# 07_-_SD.net
KiCad netlist of a schematic drawn in Altium Designer
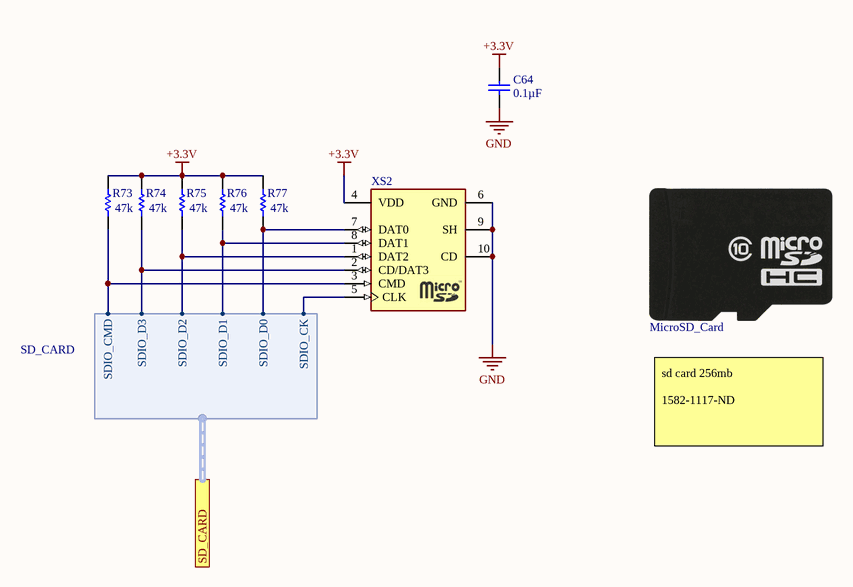
[diagram p0: [07] - SD.SchDoc]

(export (version "E")
  (design (tool "Eeschema 10.0.6"))
  (components
    (comp (ref "*1")
      (value "MicroSD_Card")
      (fields
        (field (name "MANUFACTURER") "Apacer")
        (field (name "MANUFACTURER PART NUMBER") "AP-MSD256ISI-1T")
      )
      (libsource (lib "Light_Control_BM-v.1.0-2018") (part "MicroSD_Card"))
    )
    (comp (ref "C64")
      (value "Capacitor")
      (footprint "Cap 0603")
      (description "Chip Capacitor Nonpolar")
      (fields
        (field (name "MANUFACTURER") "Kemet")
        (field (name "MANUFACTURER PART NUMBER") "C0603C104K5RACTU")
        (field (name "CAPACITANCE") "0.1µF")
      )
      (libsource (lib "Altium_Library") (part "Capacitor"))
    )
    (comp (ref "R73")
      (value "Res1")
      (footprint "Res-0603")
      (description "Chip Resistor")
      (fields
        (field (name "MANUFACTURER") "Panasonic")
        (field (name "MANUFACTURER PART NUMBER") "ERJ-3EKF4702V")
        (field (name "RESISTANCE") "47k")
      )
      (libsource (lib "Altium_Library") (part "Res1"))
    )
    (comp (ref "R74")
      (value "Res1")
      (footprint "Res-0603")
      (description "Chip Resistor")
      (fields
        (field (name "MANUFACTURER") "Panasonic")
        (field (name "MANUFACTURER PART NUMBER") "ERJ-3EKF4702V")
        (field (name "RESISTANCE") "47k")
      )
      (libsource (lib "Altium_Library") (part "Res1"))
    )
    (comp (ref "R75")
      (value "Res1")
      (footprint "Res-0603")
      (description "Chip Resistor")
      (fields
        (field (name "MANUFACTURER") "Panasonic")
        (field (name "MANUFACTURER PART NUMBER") "ERJ-3EKF4702V")
        (field (name "RESISTANCE") "47k")
      )
      (libsource (lib "Altium_Library") (part "Res1"))
    )
    (comp (ref "R76")
      (value "Res1")
      (footprint "Res-0603")
      (description "Chip Resistor")
      (fields
        (field (name "MANUFACTURER") "Panasonic")
        (field (name "MANUFACTURER PART NUMBER") "ERJ-3EKF4702V")
        (field (name "RESISTANCE") "47k")
      )
      (libsource (lib "Altium_Library") (part "Res1"))
    )
    (comp (ref "R77")
      (value "Res1")
      (footprint "Res-0603")
      (description "Chip Resistor")
      (fields
        (field (name "MANUFACTURER") "Panasonic")
        (field (name "MANUFACTURER PART NUMBER") "ERJ-3EKF4702V")
        (field (name "RESISTANCE") "47k")
      )
      (libsource (lib "Altium_Library") (part "Res1"))
    )
    (comp (ref "XS2")
      (value "~")
      (footprint "MICROSD")
      (description "=Description")
      (fields (field (name "MANUFACTURER") "Molex") (field (name "MANUFACTURER PART NUMBER") "105162-0001"))
      (libsource (lib "CVC_Meter") (part "MICROSD"))
    )
  )
  (nets
    (net (code "2") (name "+3.3V") (class "Default")
      (node (ref "C64") (pin "2") (pinfunction "2_2") (pintype "passive"))
      (node (ref "R73") (pin "2") (pinfunction "2_2") (pintype "passive"))
      (node (ref "R74") (pin "2") (pinfunction "2_2") (pintype "passive"))
      (node (ref "R75") (pin "2") (pinfunction "2_2") (pintype "passive"))
      (node (ref "R76") (pin "2") (pinfunction "2_2") (pintype "passive"))
      (node (ref "R77") (pin "2") (pinfunction "2_2") (pintype "passive"))
      (node (ref "XS2") (pin "4") (pinfunction "VDD_4") (pintype "power_in"))
    )
    (net (code "3") (name "/SDIO_CK") (class "Default")
      (node (ref "XS2") (pin "5") (pinfunction "CLK_5") (pintype "input"))
    )
    (net (code "4") (name "/SDIO_CMD") (class "Default")
      (node (ref "R73") (pin "1") (pinfunction "1_1") (pintype "passive"))
      (node (ref "XS2") (pin "3") (pinfunction "CMD_3") (pintype "input"))
    )
    (net (code "5") (name "/SDIO_D0") (class "Default")
      (node (ref "R77") (pin "1") (pinfunction "1_1") (pintype "passive"))
      (node (ref "XS2") (pin "7") (pinfunction "DAT0_7") (pintype "bidirectional"))
    )
    (net (code "6") (name "/SDIO_D1") (class "Default")
      (node (ref "R76") (pin "1") (pinfunction "1_1") (pintype "passive"))
      (node (ref "XS2") (pin "8") (pinfunction "DAT1_8") (pintype "bidirectional"))
    )
    (net (code "7") (name "/SDIO_D2") (class "Default")
      (node (ref "R75") (pin "1") (pinfunction "1_1") (pintype "passive"))
      (node (ref "XS2") (pin "1") (pinfunction "DAT2_1") (pintype "bidirectional"))
    )
    (net (code "8") (name "/SDIO_D3") (class "Default")
      (node (ref "R74") (pin "1") (pinfunction "1_1") (pintype "passive"))
      (node (ref "XS2") (pin "2") (pinfunction "CD/DAT3_2") (pintype "bidirectional"))
    )
    (net (code "10") (name "GND") (class "Default")
      (node (ref "C64") (pin "1") (pinfunction "1_1") (pintype "passive"))
      (node (ref "XS2") (pin "10") (pinfunction "CD_10") (pintype "passive"))
      (node (ref "XS2") (pin "6") (pinfunction "GND_6") (pintype "power_in"))
      (node (ref "XS2") (pin "9") (pinfunction "SH_9") (pintype "passive"))
    )
  )
)
